# 2012_carte_alim_SCHEMA.net
KiCad netlist of a schematic drawn in Altium Designer
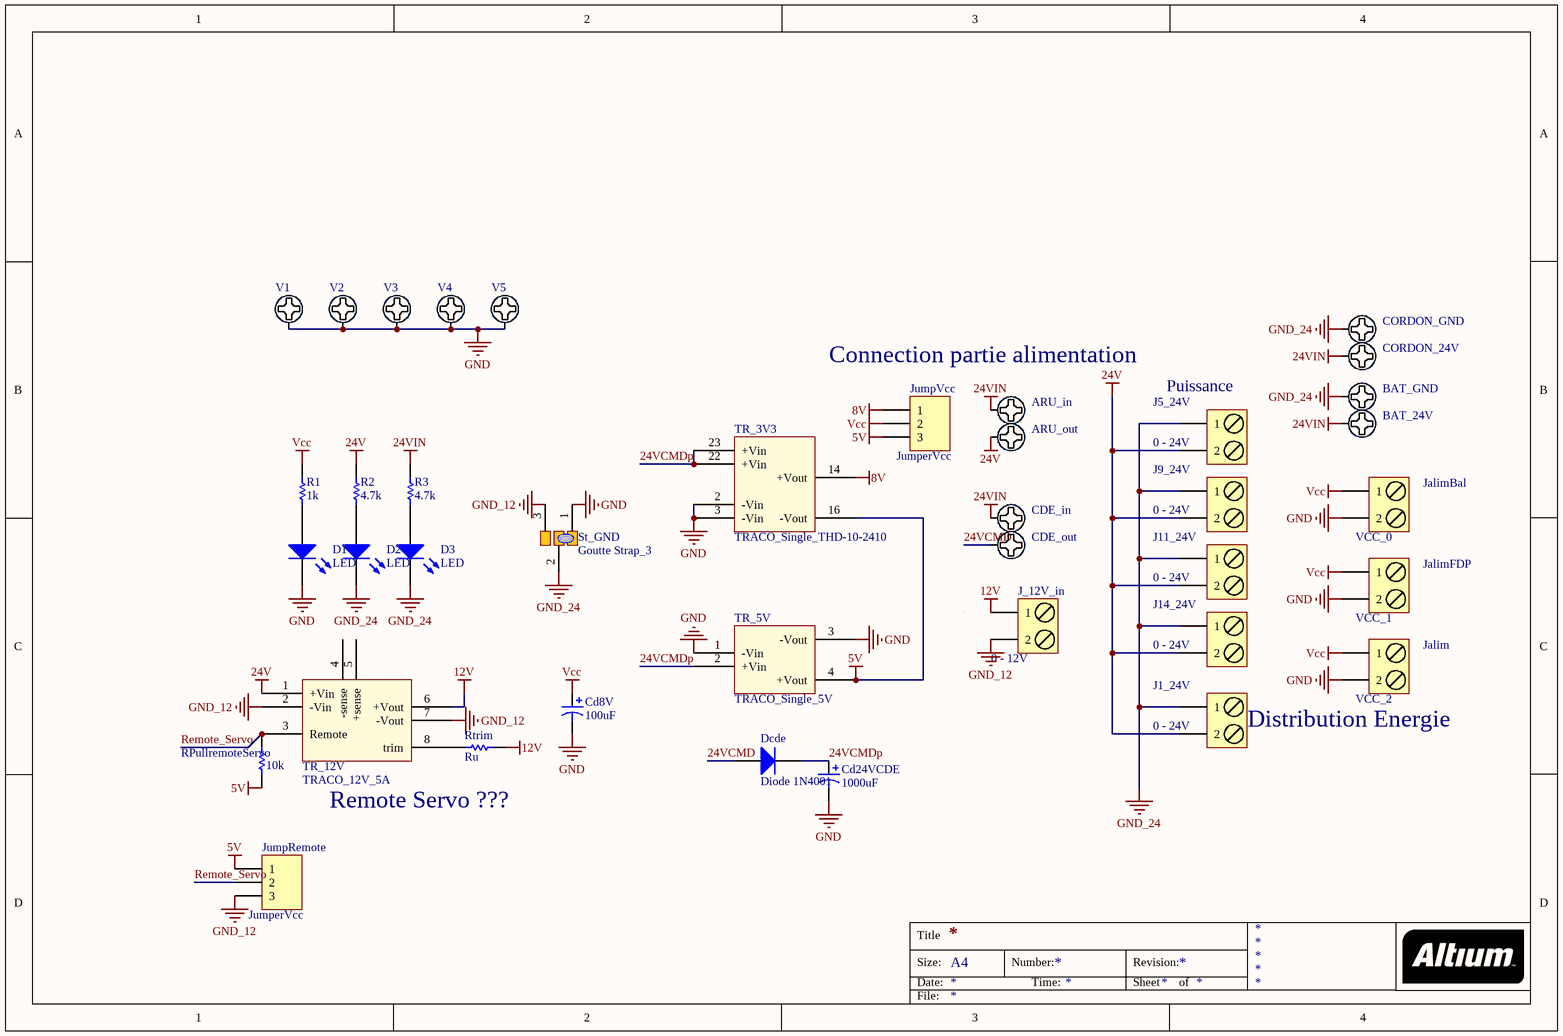
[diagram p0: 2012_carte_alim_SCHEMA.SchDoc]

(export (version "E")
  (design (tool "Eeschema 10.0.6"))
  (components
    (comp (ref "ARU_in")
      (value "Pad_M3")
      (footprint "M3x6mm")
      (description "Vis M3 X 6mm _TORX_Tête 6mm")
      (fields (field (name "PUBLISHER") "Damien Guitton"))
      (libsource (lib "_ROBOT") (part "Vis M3 X 6mm _TORX_Tête 6mm"))
    )
    (comp (ref "ARU_out")
      (value "Pad_M3")
      (footprint "M3x6mm")
      (description "Vis M3 X 6mm _TORX_Tête 6mm")
      (fields (field (name "PUBLISHER") "Damien Guitton"))
      (libsource (lib "_ROBOT") (part "Vis M3 X 6mm _TORX_Tête 6mm"))
    )
    (comp (ref "BAT_24V")
      (value "Pad_M3")
      (footprint "M3x6mm")
      (description "Vis M3 X 6mm _TORX_Tête 6mm")
      (fields (field (name "PUBLISHER") "Damien Guitton"))
      (libsource (lib "_ROBOT") (part "Vis M3 X 6mm _TORX_Tête 6mm"))
    )
    (comp (ref "BAT_GND")
      (value "Pad_M3")
      (footprint "M3x6mm")
      (description "Vis M3 X 6mm _TORX_Tête 6mm")
      (fields (field (name "PUBLISHER") "Damien Guitton"))
      (libsource (lib "_ROBOT") (part "Vis M3 X 6mm _TORX_Tête 6mm"))
    )
    (comp (ref "Cd8V")
      (value "100uF")
      (footprint "CAPPR5-10X12.5_3D")
      (description "Polarized Capacitor")
      (libsource (lib "_ROBOT") (part "Condensateur Polarise Traversant"))
    )
    (comp (ref "Cd24VCDE")
      (value "1000uF")
      (footprint "CAPPR7.5-18X40")
      (description "Polarized Capacitor")
      (libsource (lib "_ROBOT") (part "Condensateur Polarise Traversant"))
    )
    (comp (ref "CDE_in")
      (value "Pad_M3")
      (footprint "M3x6mm")
      (description "Vis M3 X 6mm _TORX_Tête 6mm")
      (fields (field (name "PUBLISHER") "Damien Guitton"))
      (libsource (lib "_ROBOT") (part "Vis M3 X 6mm _TORX_Tête 6mm"))
    )
    (comp (ref "CDE_out")
      (value "Pad_M3")
      (footprint "M3x6mm")
      (description "Vis M3 X 6mm _TORX_Tête 6mm")
      (fields (field (name "PUBLISHER") "Damien Guitton"))
      (libsource (lib "_ROBOT") (part "Vis M3 X 6mm _TORX_Tête 6mm"))
    )
    (comp (ref "CORDON_24V")
      (value "Pad_M3")
      (footprint "M3x6mm")
      (description "Vis M3 X 6mm _TORX_Tête 6mm")
      (fields (field (name "PUBLISHER") "Damien Guitton"))
      (libsource (lib "_ROBOT") (part "Vis M3 X 6mm _TORX_Tête 6mm"))
    )
    (comp (ref "CORDON_GND")
      (value "Pad_M3")
      (footprint "M3x6mm")
      (description "Vis M3 X 6mm _TORX_Tête 6mm")
      (fields (field (name "PUBLISHER") "Damien Guitton"))
      (libsource (lib "_ROBOT") (part "Vis M3 X 6mm _TORX_Tête 6mm"))
    )
    (comp (ref "D1")
      (value "LED")
      (footprint "LED_0805")
      (description "Typical LED")
      (fields (field (name "PUBLISHER") "Altium Limited"))
      (libsource (lib "_ROBOT") (part "LED"))
    )
    (comp (ref "D2")
      (value "LED")
      (footprint "LED_0805")
      (description "Typical LED")
      (fields (field (name "PUBLISHER") "Altium Limited"))
      (libsource (lib "_ROBOT") (part "LED"))
    )
    (comp (ref "D3")
      (value "LED")
      (footprint "LED_0805")
      (description "Typical LED")
      (fields (field (name "PUBLISHER") "Altium Limited"))
      (libsource (lib "_ROBOT") (part "LED"))
    )
    (comp (ref "Dcde")
      (value "Diode 1N4001")
      (footprint "DIO10.46-5.3x2.8")
      (description "1 Amp General Purpose Rectifier")
      (fields (field (name "PUBLISHER") "Altium Limited"))
      (libsource (lib "Miscellaneous Devices") (part "Diode 1N4001"))
    )
    (comp (ref "J1_24V")
      (value "0 - 24V")
      (footprint "BORNIER2_FEM_COUDE")
      (description "Terminal blocks, 2 pins, pitch=5mm")
      (libsource (lib "miniprojet") (part "BORNIER2"))
    )
    (comp (ref "J5_24V")
      (value "0 - 24V")
      (footprint "BORNIER2_FEM_COUDE")
      (description "Terminal blocks, 2 pins, pitch=5mm")
      (libsource (lib "miniprojet") (part "BORNIER2"))
    )
    (comp (ref "J9_24V")
      (value "0 - 24V")
      (footprint "BORNIER2_FEM_COUDE")
      (description "Terminal blocks, 2 pins, pitch=5mm")
      (libsource (lib "miniprojet") (part "BORNIER2"))
    )
    (comp (ref "J11_24V")
      (value "0 - 24V")
      (footprint "BORNIER2_FEM_COUDE")
      (description "Terminal blocks, 2 pins, pitch=5mm")
      (libsource (lib "miniprojet") (part "BORNIER2"))
    )
    (comp (ref "J14_24V")
      (value "0 - 24V")
      (footprint "BORNIER2_FEM_COUDE")
      (description "Terminal blocks, 2 pins, pitch=5mm")
      (libsource (lib "miniprojet") (part "BORNIER2"))
    )
    (comp (ref "Jalim")
      (value "VCC_2")
      (footprint "Bornier_2_pas 5.08mm")
      (description "Terminal blocks, 2 pins, pitch=5mm")
      (libsource (lib "miniprojet") (part "BORNIER2"))
    )
    (comp (ref "JalimBal")
      (value "VCC_0")
      (footprint "BORNIER2")
      (description "Terminal blocks, 2 pins, pitch=5mm")
      (libsource (lib "miniprojet") (part "BORNIER2"))
    )
    (comp (ref "JalimFDP")
      (value "VCC_1")
      (footprint "BORNIER2")
      (description "Terminal blocks, 2 pins, pitch=5mm")
      (libsource (lib "miniprojet") (part "BORNIER2"))
    )
    (comp (ref "JumpRemote")
      (value "JumperVcc")
      (footprint "HE14_3")
      (description "Header, 3-Pin")
      (fields (field (name "PUBLISHER") "Altium Limited"))
      (libsource (lib "Connecteur") (part "BARRETTE3"))
    )
    (comp (ref "JumpVcc")
      (value "JumperVcc")
      (footprint "HE14_3")
      (description "Header, 3-Pin")
      (fields (field (name "PUBLISHER") "Altium Limited"))
      (libsource (lib "Connecteur") (part "BARRETTE3"))
    )
    (comp (ref "J_12V_in")
      (value "0 - 12V")
      (footprint "BORNIER2_FEM_COUDE")
      (description "Terminal blocks, 2 pins, pitch=5mm")
      (libsource (lib "miniprojet") (part "BORNIER2"))
    )
    (comp (ref "R1")
      (value "1k")
      (footprint "R1206_N")
      (description "Resistor")
      (fields (field (name "PUBLISHER") "Altium Limited"))
      (libsource (lib "_ROBOT") (part "Resistor"))
    )
    (comp (ref "R2")
      (value "4.7k")
      (footprint "R1206_N")
      (description "Resistor")
      (fields (field (name "PUBLISHER") "Altium Limited"))
      (libsource (lib "_ROBOT") (part "Resistor"))
    )
    (comp (ref "R3")
      (value "4.7k")
      (footprint "R1206_N")
      (description "Resistor")
      (fields (field (name "PUBLISHER") "Altium Limited"))
      (libsource (lib "_ROBOT") (part "Resistor"))
    )
    (comp (ref "RPullremoteServo")
      (value "10k")
      (footprint "R1206_N")
      (description "Resistor")
      (fields (field (name "PUBLISHER") "Altium Limited"))
      (libsource (lib "_ROBOT") (part "Resistor"))
    )
    (comp (ref "Rtrim")
      (value "Ru")
      (footprint "R1206_N")
      (description "Resistor")
      (fields (field (name "PUBLISHER") "Altium Limited"))
      (libsource (lib "_ROBOT") (part "Resistor"))
    )
    (comp (ref "St_GND")
      (value "Goutte Strap_3")
      (footprint "Goutte Strap_3")
      (fields (field (name "PUBLISHER") "Damien Guitton"))
      (libsource (lib "DG_Connecteur") (part "Goutte Strap_3"))
    )
    (comp (ref "TR_3V3")
      (value "TRACO_Single_THD-10-2410")
      (footprint "TRACO_Single - 3.3V 3A THD-10-2410")
      (libsource (lib "_ROBOT") (part "TRACO_Single_THD-10-2410"))
    )
    (comp (ref "TR_5V")
      (value "TRACO_Single_5V")
      (footprint "TRACO_Single")
      (libsource (lib "Robot2010") (part "TRACO_Single"))
    )
    (comp (ref "TR_12V")
      (value "TRACO_12V_5A")
      (footprint "TRACO_SIMPLE_12V_5A")
      (libsource (lib "_ROBOT") (part "TRACO_12V_5A"))
    )
    (comp (ref "V1")
      (value "Pad_M3")
      (footprint "M3x6mm")
      (description "Vis M3 X 6mm _TORX_Tête 6mm")
      (fields (field (name "PUBLISHER") "Damien Guitton"))
      (libsource (lib "_ROBOT") (part "Vis M3 X 6mm _TORX_Tête 6mm"))
    )
    (comp (ref "V2")
      (value "Pad_M3")
      (footprint "M3x6mm")
      (description "Vis M3 X 6mm _TORX_Tête 6mm")
      (fields (field (name "PUBLISHER") "Damien Guitton"))
      (libsource (lib "_ROBOT") (part "Vis M3 X 6mm _TORX_Tête 6mm"))
    )
    (comp (ref "V3")
      (value "Pad_M3")
      (footprint "M3x6mm")
      (description "Vis M3 X 6mm _TORX_Tête 6mm")
      (fields (field (name "PUBLISHER") "Damien Guitton"))
      (libsource (lib "_ROBOT") (part "Vis M3 X 6mm _TORX_Tête 6mm"))
    )
    (comp (ref "V4")
      (value "Pad_M3")
      (footprint "M3x6mm")
      (description "Vis M3 X 6mm _TORX_Tête 6mm")
      (fields (field (name "PUBLISHER") "Damien Guitton"))
      (libsource (lib "_ROBOT") (part "Vis M3 X 6mm _TORX_Tête 6mm"))
    )
    (comp (ref "V5")
      (value "Pad_M3")
      (footprint "M3x6mm")
      (description "Vis M3 X 6mm _TORX_Tête 6mm")
      (fields (field (name "PUBLISHER") "Damien Guitton"))
      (libsource (lib "_ROBOT") (part "Vis M3 X 6mm _TORX_Tête 6mm"))
    )
  )
  (nets
    (net (code "1") (name "/24VCMD") (class "Default")
      (node (ref "CDE_out") (pin "1") (pinfunction "1_1") (pintype "passive"))
      (node (ref "Dcde") (pin "1") (pinfunction "A_1") (pintype "passive"))
    )
    (net (code "2") (name "/24VCMDp") (class "Default")
      (node (ref "Cd24VCDE") (pin "1") (pinfunction "1_1") (pintype "passive"))
      (node (ref "Dcde") (pin "2") (pinfunction "K_2") (pintype "passive"))
      (node (ref "TR_3V3") (pin "22") (pinfunction "+Vin_22") (pintype "passive"))
      (node (ref "TR_3V3") (pin "23") (pinfunction "+Vin_23") (pintype "passive"))
      (node (ref "TR_5V") (pin "2") (pinfunction "+Vin_2") (pintype "passive"))
    )
    (net (code "3") (name "/Remote_Servo") (class "Default")
      (node (ref "JumpRemote") (pin "2") (pinfunction "2_2") (pintype "passive"))
      (node (ref "RPullremoteServo") (pin "1") (pinfunction "1_1") (pintype "passive"))
      (node (ref "TR_12V") (pin "3") (pinfunction "Remote_3") (pintype "passive"))
    )
    (net (code "4") (name "5V") (class "Default")
      (node (ref "JumpRemote") (pin "1") (pinfunction "1_1") (pintype "passive"))
      (node (ref "JumpVcc") (pin "3") (pinfunction "3_3") (pintype "passive"))
      (node (ref "RPullremoteServo") (pin "2") (pinfunction "2_2") (pintype "passive"))
      (node (ref "TR_3V3") (pin "16") (pinfunction "-Vout_16") (pintype "passive"))
      (node (ref "TR_5V") (pin "4") (pinfunction "+Vout_4") (pintype "passive"))
    )
    (net (code "5") (name "8V") (class "Default")
      (node (ref "JumpVcc") (pin "1") (pinfunction "1_1") (pintype "passive"))
      (node (ref "TR_3V3") (pin "14") (pinfunction "+Vout_14") (pintype "passive"))
    )
    (net (code "6") (name "12V") (class "Default")
      (node (ref "J_12V_in") (pin "1") (pinfunction "1_1") (pintype "passive"))
      (node (ref "Rtrim") (pin "2") (pinfunction "2_2") (pintype "passive"))
      (node (ref "TR_12V") (pin "6") (pinfunction "+Vout_6") (pintype "passive"))
    )
    (net (code "7") (name "24V") (class "Default")
      (node (ref "ARU_out") (pin "1") (pinfunction "1_1") (pintype "passive"))
      (node (ref "J11_24V") (pin "2") (pinfunction "2_2") (pintype "passive"))
      (node (ref "J14_24V") (pin "2") (pinfunction "2_2") (pintype "passive"))
      (node (ref "J1_24V") (pin "2") (pinfunction "2_2") (pintype "passive"))
      (node (ref "J5_24V") (pin "2") (pinfunction "2_2") (pintype "passive"))
      (node (ref "J9_24V") (pin "2") (pinfunction "2_2") (pintype "passive"))
      (node (ref "R2") (pin "1") (pinfunction "1_1") (pintype "passive"))
      (node (ref "TR_12V") (pin "1") (pinfunction "+Vin_1") (pintype "passive"))
    )
    (net (code "8") (name "24VIN") (class "Default")
      (node (ref "ARU_in") (pin "1") (pinfunction "1_1") (pintype "passive"))
      (node (ref "BAT_24V") (pin "1") (pinfunction "1_1") (pintype "passive"))
      (node (ref "CDE_in") (pin "1") (pinfunction "1_1") (pintype "passive"))
      (node (ref "CORDON_24V") (pin "1") (pinfunction "1_1") (pintype "passive"))
      (node (ref "R3") (pin "1") (pinfunction "1_1") (pintype "passive"))
    )
    (net (code "9") (name "GND") (class "Default")
      (node (ref "Cd24VCDE") (pin "2") (pinfunction "2_2") (pintype "passive"))
      (node (ref "Cd8V") (pin "2") (pinfunction "2_2") (pintype "passive"))
      (node (ref "D1") (pin "2") (pinfunction "K_2") (pintype "passive"))
      (node (ref "Jalim") (pin "2") (pinfunction "2_2") (pintype "passive"))
      (node (ref "JalimBal") (pin "2") (pinfunction "2_2") (pintype "passive"))
      (node (ref "JalimFDP") (pin "2") (pinfunction "2_2") (pintype "passive"))
      (node (ref "St_GND") (pin "1") (pinfunction "1_1") (pintype "passive"))
      (node (ref "TR_3V3") (pin "2") (pinfunction "-Vin_2") (pintype "passive"))
      (node (ref "TR_3V3") (pin "3") (pinfunction "-Vin_3") (pintype "passive"))
      (node (ref "TR_5V") (pin "1") (pinfunction "-Vin_1") (pintype "passive"))
      (node (ref "TR_5V") (pin "3") (pinfunction "-Vout_3") (pintype "passive"))
      (node (ref "V1") (pin "1") (pinfunction "1_1") (pintype "passive"))
      (node (ref "V2") (pin "1") (pinfunction "1_1") (pintype "passive"))
      (node (ref "V3") (pin "1") (pinfunction "1_1") (pintype "passive"))
      (node (ref "V4") (pin "1") (pinfunction "1_1") (pintype "passive"))
      (node (ref "V5") (pin "1") (pinfunction "1_1") (pintype "passive"))
    )
    (net (code "10") (name "GND_12") (class "Default")
      (node (ref "J_12V_in") (pin "2") (pinfunction "2_2") (pintype "passive"))
      (node (ref "JumpRemote") (pin "3") (pinfunction "3_3") (pintype "passive"))
      (node (ref "St_GND") (pin "3") (pinfunction "3_3") (pintype "passive"))
      (node (ref "TR_12V") (pin "2") (pinfunction "-Vin_2") (pintype "passive"))
      (node (ref "TR_12V") (pin "7") (pinfunction "-Vout_7") (pintype "passive"))
    )
    (net (code "11") (name "GND_24") (class "Default")
      (node (ref "BAT_GND") (pin "1") (pinfunction "1_1") (pintype "passive"))
      (node (ref "CORDON_GND") (pin "1") (pinfunction "1_1") (pintype "passive"))
      (node (ref "D2") (pin "2") (pinfunction "K_2") (pintype "passive"))
      (node (ref "D3") (pin "2") (pinfunction "K_2") (pintype "passive"))
      (node (ref "J11_24V") (pin "1") (pinfunction "1_1") (pintype "passive"))
      (node (ref "J14_24V") (pin "1") (pinfunction "1_1") (pintype "passive"))
      (node (ref "J1_24V") (pin "1") (pinfunction "1_1") (pintype "passive"))
      (node (ref "J5_24V") (pin "1") (pinfunction "1_1") (pintype "passive"))
      (node (ref "J9_24V") (pin "1") (pinfunction "1_1") (pintype "passive"))
      (node (ref "St_GND") (pin "2") (pinfunction "2_2") (pintype "passive"))
    )
    (net (code "12") (name "Net-(D1-A)") (class "Default")
      (node (ref "D1") (pin "1") (pinfunction "A_1") (pintype "passive"))
      (node (ref "R1") (pin "2") (pinfunction "2_2") (pintype "passive"))
    )
    (net (code "13") (name "Net-(D2-A)") (class "Default")
      (node (ref "D2") (pin "1") (pinfunction "A_1") (pintype "passive"))
      (node (ref "R2") (pin "2") (pinfunction "2_2") (pintype "passive"))
    )
    (net (code "14") (name "Net-(D3-A)") (class "Default")
      (node (ref "D3") (pin "1") (pinfunction "A_1") (pintype "passive"))
      (node (ref "R3") (pin "2") (pinfunction "2_2") (pintype "passive"))
    )
    (net (code "15") (name "Net-(TR_12V-trim)") (class "Default")
      (node (ref "Rtrim") (pin "1") (pinfunction "1_1") (pintype "passive"))
      (node (ref "TR_12V") (pin "8") (pinfunction "trim_8") (pintype "passive"))
    )
    (net (code "16") (name "Vcc") (class "Default")
      (node (ref "Cd8V") (pin "1") (pinfunction "1_1") (pintype "passive"))
      (node (ref "Jalim") (pin "1") (pinfunction "1_1") (pintype "passive"))
      (node (ref "JalimBal") (pin "1") (pinfunction "1_1") (pintype "passive"))
      (node (ref "JalimFDP") (pin "1") (pinfunction "1_1") (pintype "passive"))
      (node (ref "JumpVcc") (pin "2") (pinfunction "2_2") (pintype "passive"))
      (node (ref "R1") (pin "1") (pinfunction "1_1") (pintype "passive"))
    )
    (net (code "17") (name "unconnected-(TR_12V-+sense-Pad5)") (class "Default")
      (node (ref "TR_12V") (pin "5") (pinfunction "+sense_5") (pintype "passive"))
    )
    (net (code "18") (name "unconnected-(TR_12V--sense-Pad4)") (class "Default")
      (node (ref "TR_12V") (pin "4") (pinfunction "-sense_4") (pintype "passive"))
    )
  )
)
